# TUDSSL_condenar__Hardware_PCBs_Mainboard.net
KiCad netlist of a schematic drawn in Altium Designer
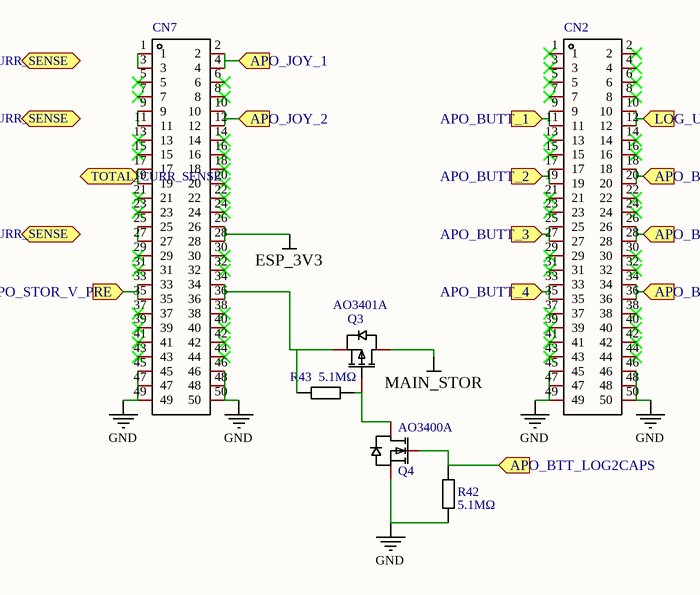
[diagram p0: TUDSSL_condenar__Hardware_PCBs_Mainboard_Board_TUD-V2-EnergyHarvestingConsole_TUD-EnergyHarvestingConsole_1__5_Logging.schdoc]

(export (version "E")
  (design (tool "Eeschema 10.0.6"))
  (components
    (comp (ref "CN2")
      (value "DF40C-50DS-0.4V(51)")
      (fields (field (name "MANUFACTURER") "HRS(广濑)"))
      (libsource (lib "altium-import") (part "root_0_DF40C-50DS-0.4V(51)_"))
    )
    (comp (ref "CN7")
      (value "DF40C-50DS-0.4V(51)")
      (fields (field (name "MANUFACTURER") "HRS(广濑)"))
      (libsource (lib "altium-import") (part "root_0_DF40C-50DS-0.4V(51)_"))
    )
    (comp (ref "Q3")
      (value "AO3401A")
      (fields (field (name "NAME") "AO3401A") (field (name "MANUFACTURER") "AOS"))
      (libsource (lib "altium-import") (part "root_1_AO3401A_"))
    )
    (comp (ref "Q4")
      (value "AO3400A")
      (fields (field (name "NAME") "AO3400A") (field (name "MANUFACTURER") "HUASHUO(华朔)"))
      (libsource (lib "altium-import") (part "root_0_mirrored_AO3400A_"))
    )
    (comp (ref "R42")
      (value "5.1MΩ")
      (fields
        (field (name "NAME") "5.1MΩ")
        (field (name "MANUFACTURER") "UniOhm")
        (field (name "MANUFACTURER PART") "0603WAF5104T5E")
      )
      (libsource (lib "altium-import") (part "root_1_0603WAF5104T5E_"))
    )
    (comp (ref "R43")
      (value "5.1MΩ")
      (fields
        (field (name "NAME") "5.1MΩ")
        (field (name "MANUFACTURER") "UniOhm")
        (field (name "MANUFACTURER PART") "0603WAF5104T5E")
      )
      (libsource (lib "altium-import") (part "root_0_0603WAF5104T5E_"))
    )
  )
  (nets
    (net (code "1") (name "/APO_BTT_LOG2CAPS") (class "Default")
      (node (ref "Q4") (pin "1") (pinfunction "G_1") (pintype "passive"))
      (node (ref "R42") (pin "1") (pinfunction "1_1") (pintype "passive"))
    )
    (net (code "2") (name "/APO_BUTT_1") (class "Default")
      (node (ref "CN2") (pin "11") (pinfunction "11_11") (pintype "passive"))
      (node (ref "CN2") (pin "9") (pinfunction "9_9") (pintype "passive"))
    )
    (net (code "3") (name "/APO_BUTT_2") (class "Default")
      (node (ref "CN2") (pin "17") (pinfunction "17_17") (pintype "passive"))
      (node (ref "CN2") (pin "19") (pinfunction "19_19") (pintype "passive"))
    )
    (net (code "4") (name "/APO_BUTT_3") (class "Default")
      (node (ref "CN2") (pin "25") (pinfunction "25_25") (pintype "passive"))
      (node (ref "CN2") (pin "27") (pinfunction "27_27") (pintype "passive"))
    )
    (net (code "5") (name "/APO_BUTT_4") (class "Default")
      (node (ref "CN2") (pin "33") (pinfunction "33_33") (pintype "passive"))
      (node (ref "CN2") (pin "35") (pinfunction "35_35") (pintype "passive"))
    )
    (net (code "6") (name "/APO_BUTT_5") (class "Default")
      (node (ref "CN2") (pin "34") (pinfunction "34_34") (pintype "passive"))
      (node (ref "CN2") (pin "36") (pinfunction "36_36") (pintype "passive"))
    )
    (net (code "7") (name "/APO_BUTT_6") (class "Default")
      (node (ref "CN2") (pin "26") (pinfunction "26_26") (pintype "passive"))
      (node (ref "CN2") (pin "28") (pinfunction "28_28") (pintype "passive"))
    )
    (net (code "8") (name "/APO_BUTT_7") (class "Default")
      (node (ref "CN2") (pin "18") (pinfunction "18_18") (pintype "passive"))
      (node (ref "CN2") (pin "20") (pinfunction "20_20") (pintype "passive"))
    )
    (net (code "9") (name "/APO_JOY_1") (class "Default")
      (node (ref "CN7") (pin "2") (pinfunction "2_2") (pintype "passive"))
      (node (ref "CN7") (pin "4") (pinfunction "4_4") (pintype "passive"))
    )
    (net (code "10") (name "/APO_JOY_2") (class "Default")
      (node (ref "CN7") (pin "10") (pinfunction "10_10") (pintype "passive"))
      (node (ref "CN7") (pin "12") (pinfunction "12_12") (pintype "passive"))
    )
    (net (code "11") (name "/APO_STOR_V_PRE") (class "Default")
      (node (ref "CN7") (pin "33") (pinfunction "33_33") (pintype "passive"))
      (node (ref "CN7") (pin "35") (pinfunction "35_35") (pintype "passive"))
    )
    (net (code "14") (name "/LOG_UART_RX") (class "Default")
      (node (ref "CN2") (pin "10") (pinfunction "10_10") (pintype "passive"))
      (node (ref "CN2") (pin "12") (pinfunction "12_12") (pintype "passive"))
    )
    (net (code "17") (name "ESP_3V3") (class "Default")
      (node (ref "CN7") (pin "26") (pinfunction "26_26") (pintype "passive"))
      (node (ref "CN7") (pin "28") (pinfunction "28_28") (pintype "passive"))
    )
    (net (code "18") (name "GND") (class "Default")
      (node (ref "CN2") (pin "45") (pinfunction "45_45") (pintype "passive"))
      (node (ref "CN2") (pin "46") (pinfunction "46_46") (pintype "passive"))
      (node (ref "CN2") (pin "47") (pinfunction "47_47") (pintype "passive"))
      (node (ref "CN2") (pin "48") (pinfunction "48_48") (pintype "passive"))
      (node (ref "CN2") (pin "49") (pinfunction "49_49") (pintype "passive"))
      (node (ref "CN2") (pin "50") (pinfunction "50_50") (pintype "passive"))
      (node (ref "CN7") (pin "45") (pinfunction "45_45") (pintype "passive"))
      (node (ref "CN7") (pin "46") (pinfunction "46_46") (pintype "passive"))
      (node (ref "CN7") (pin "47") (pinfunction "47_47") (pintype "passive"))
      (node (ref "CN7") (pin "48") (pinfunction "48_48") (pintype "passive"))
      (node (ref "CN7") (pin "49") (pinfunction "49_49") (pintype "passive"))
      (node (ref "CN7") (pin "50") (pinfunction "50_50") (pintype "passive"))
      (node (ref "Q4") (pin "2") (pinfunction "S_2") (pintype "passive"))
      (node (ref "R42") (pin "2") (pinfunction "2_2") (pintype "passive"))
    )
    (net (code "19") (name "MAIN_STOR") (class "Default")
      (node (ref "Q3") (pin "3") (pinfunction "D_3") (pintype "passive"))
    )
    (net (code "20") (name "Net-(CN7-Pad1)") (class "Default")
      (node (ref "CN7") (pin "1") (pinfunction "1_1") (pintype "passive"))
      (node (ref "CN7") (pin "3") (pinfunction "3_3") (pintype "passive"))
    )
    (net (code "21") (name "Net-(CN7-Pad11)") (class "Default")
      (node (ref "CN7") (pin "11") (pinfunction "11_11") (pintype "passive"))
      (node (ref "CN7") (pin "9") (pinfunction "9_9") (pintype "passive"))
    )
    (net (code "22") (name "Net-(CN7-Pad17)") (class "Default")
      (node (ref "CN7") (pin "17") (pinfunction "17_17") (pintype "passive"))
      (node (ref "CN7") (pin "19") (pinfunction "19_19") (pintype "passive"))
    )
    (net (code "23") (name "Net-(CN7-Pad25)") (class "Default")
      (node (ref "CN7") (pin "25") (pinfunction "25_25") (pintype "passive"))
      (node (ref "CN7") (pin "27") (pinfunction "27_27") (pintype "passive"))
    )
    (net (code "24") (name "Net-(Q3-G)") (class "Default")
      (node (ref "Q3") (pin "1") (pinfunction "G_1") (pintype "passive"))
      (node (ref "Q4") (pin "3") (pinfunction "D_3") (pintype "passive"))
      (node (ref "R43") (pin "1") (pinfunction "1_1") (pintype "passive"))
    )
    (net (code "25") (name "Net-(Q3-S)") (class "Default")
      (node (ref "CN7") (pin "34") (pinfunction "34_34") (pintype "passive"))
      (node (ref "CN7") (pin "36") (pinfunction "36_36") (pintype "passive"))
      (node (ref "Q3") (pin "2") (pinfunction "S_2") (pintype "passive"))
      (node (ref "R43") (pin "2") (pinfunction "2_2") (pintype "passive"))
    )
    (net (code "26") (name "unconnected-(CN2-Pad1)") (class "Default")
      (node (ref "CN2") (pin "1") (pinfunction "1_1") (pintype "passive+no_connect"))
    )
    (net (code "27") (name "unconnected-(CN2-Pad2)") (class "Default")
      (node (ref "CN2") (pin "2") (pinfunction "2_2") (pintype "passive+no_connect"))
    )
    (net (code "28") (name "unconnected-(CN2-Pad3)") (class "Default")
      (node (ref "CN2") (pin "3") (pinfunction "3_3") (pintype "passive+no_connect"))
    )
    (net (code "29") (name "unconnected-(CN2-Pad4)") (class "Default")
      (node (ref "CN2") (pin "4") (pinfunction "4_4") (pintype "passive+no_connect"))
    )
    (net (code "30") (name "unconnected-(CN2-Pad5)") (class "Default")
      (node (ref "CN2") (pin "5") (pinfunction "5_5") (pintype "passive+no_connect"))
    )
    (net (code "31") (name "unconnected-(CN2-Pad6)") (class "Default")
      (node (ref "CN2") (pin "6") (pinfunction "6_6") (pintype "passive+no_connect"))
    )
    (net (code "32") (name "unconnected-(CN2-Pad7)") (class "Default")
      (node (ref "CN2") (pin "7") (pinfunction "7_7") (pintype "passive+no_connect"))
    )
    (net (code "33") (name "unconnected-(CN2-Pad8)") (class "Default")
      (node (ref "CN2") (pin "8") (pinfunction "8_8") (pintype "passive+no_connect"))
    )
    (net (code "34") (name "unconnected-(CN2-Pad13)") (class "Default")
      (node (ref "CN2") (pin "13") (pinfunction "13_13") (pintype "passive+no_connect"))
    )
    (net (code "35") (name "unconnected-(CN2-Pad14)") (class "Default")
      (node (ref "CN2") (pin "14") (pinfunction "14_14") (pintype "passive+no_connect"))
    )
    (net (code "36") (name "unconnected-(CN2-Pad15)") (class "Default")
      (node (ref "CN2") (pin "15") (pinfunction "15_15") (pintype "passive+no_connect"))
    )
    (net (code "37") (name "unconnected-(CN2-Pad16)") (class "Default")
      (node (ref "CN2") (pin "16") (pinfunction "16_16") (pintype "passive+no_connect"))
    )
    (net (code "38") (name "unconnected-(CN2-Pad21)") (class "Default")
      (node (ref "CN2") (pin "21") (pinfunction "21_21") (pintype "passive+no_connect"))
    )
    (net (code "39") (name "unconnected-(CN2-Pad22)") (class "Default")
      (node (ref "CN2") (pin "22") (pinfunction "22_22") (pintype "passive+no_connect"))
    )
    (net (code "40") (name "unconnected-(CN2-Pad23)") (class "Default")
      (node (ref "CN2") (pin "23") (pinfunction "23_23") (pintype "passive+no_connect"))
    )
    (net (code "41") (name "unconnected-(CN2-Pad24)") (class "Default")
      (node (ref "CN2") (pin "24") (pinfunction "24_24") (pintype "passive+no_connect"))
    )
    (net (code "42") (name "unconnected-(CN2-Pad29)") (class "Default")
      (node (ref "CN2") (pin "29") (pinfunction "29_29") (pintype "passive+no_connect"))
    )
    (net (code "43") (name "unconnected-(CN2-Pad30)") (class "Default")
      (node (ref "CN2") (pin "30") (pinfunction "30_30") (pintype "passive+no_connect"))
    )
    (net (code "44") (name "unconnected-(CN2-Pad31)") (class "Default")
      (node (ref "CN2") (pin "31") (pinfunction "31_31") (pintype "passive+no_connect"))
    )
    (net (code "45") (name "unconnected-(CN2-Pad32)") (class "Default")
      (node (ref "CN2") (pin "32") (pinfunction "32_32") (pintype "passive+no_connect"))
    )
    (net (code "46") (name "unconnected-(CN2-Pad37)") (class "Default")
      (node (ref "CN2") (pin "37") (pinfunction "37_37") (pintype "passive+no_connect"))
    )
    (net (code "47") (name "unconnected-(CN2-Pad38)") (class "Default")
      (node (ref "CN2") (pin "38") (pinfunction "38_38") (pintype "passive+no_connect"))
    )
    (net (code "48") (name "unconnected-(CN2-Pad39)") (class "Default")
      (node (ref "CN2") (pin "39") (pinfunction "39_39") (pintype "passive+no_connect"))
    )
    (net (code "49") (name "unconnected-(CN2-Pad40)") (class "Default")
      (node (ref "CN2") (pin "40") (pinfunction "40_40") (pintype "passive+no_connect"))
    )
    (net (code "50") (name "unconnected-(CN2-Pad41)") (class "Default")
      (node (ref "CN2") (pin "41") (pinfunction "41_41") (pintype "passive+no_connect"))
    )
    (net (code "51") (name "unconnected-(CN2-Pad42)") (class "Default")
      (node (ref "CN2") (pin "42") (pinfunction "42_42") (pintype "passive+no_connect"))
    )
    (net (code "52") (name "unconnected-(CN2-Pad43)") (class "Default")
      (node (ref "CN2") (pin "43") (pinfunction "43_43") (pintype "passive+no_connect"))
    )
    (net (code "53") (name "unconnected-(CN2-Pad44)") (class "Default")
      (node (ref "CN2") (pin "44") (pinfunction "44_44") (pintype "passive+no_connect"))
    )
    (net (code "54") (name "unconnected-(CN7-Pad5)") (class "Default")
      (node (ref "CN7") (pin "5") (pinfunction "5_5") (pintype "passive+no_connect"))
    )
    (net (code "55") (name "unconnected-(CN7-Pad6)") (class "Default")
      (node (ref "CN7") (pin "6") (pinfunction "6_6") (pintype "passive+no_connect"))
    )
    (net (code "56") (name "unconnected-(CN7-Pad7)") (class "Default")
      (node (ref "CN7") (pin "7") (pinfunction "7_7") (pintype "passive+no_connect"))
    )
    (net (code "57") (name "unconnected-(CN7-Pad8)") (class "Default")
      (node (ref "CN7") (pin "8") (pinfunction "8_8") (pintype "passive+no_connect"))
    )
    (net (code "58") (name "unconnected-(CN7-Pad13)") (class "Default")
      (node (ref "CN7") (pin "13") (pinfunction "13_13") (pintype "passive+no_connect"))
    )
    (net (code "59") (name "unconnected-(CN7-Pad14)") (class "Default")
      (node (ref "CN7") (pin "14") (pinfunction "14_14") (pintype "passive+no_connect"))
    )
    (net (code "60") (name "unconnected-(CN7-Pad15)") (class "Default")
      (node (ref "CN7") (pin "15") (pinfunction "15_15") (pintype "passive+no_connect"))
    )
    (net (code "61") (name "unconnected-(CN7-Pad16)") (class "Default")
      (node (ref "CN7") (pin "16") (pinfunction "16_16") (pintype "passive+no_connect"))
    )
    (net (code "62") (name "unconnected-(CN7-Pad18)") (class "Default")
      (node (ref "CN7") (pin "18") (pinfunction "18_18") (pintype "passive+no_connect"))
    )
    (net (code "63") (name "unconnected-(CN7-Pad20)") (class "Default")
      (node (ref "CN7") (pin "20") (pinfunction "20_20") (pintype "passive+no_connect"))
    )
    (net (code "64") (name "unconnected-(CN7-Pad21)") (class "Default")
      (node (ref "CN7") (pin "21") (pinfunction "21_21") (pintype "passive+no_connect"))
    )
    (net (code "65") (name "unconnected-(CN7-Pad22)") (class "Default")
      (node (ref "CN7") (pin "22") (pinfunction "22_22") (pintype "passive+no_connect"))
    )
    (net (code "66") (name "unconnected-(CN7-Pad23)") (class "Default")
      (node (ref "CN7") (pin "23") (pinfunction "23_23") (pintype "passive+no_connect"))
    )
    (net (code "67") (name "unconnected-(CN7-Pad24)") (class "Default")
      (node (ref "CN7") (pin "24") (pinfunction "24_24") (pintype "passive+no_connect"))
    )
    (net (code "68") (name "unconnected-(CN7-Pad29)") (class "Default")
      (node (ref "CN7") (pin "29") (pinfunction "29_29") (pintype "passive+no_connect"))
    )
    (net (code "69") (name "unconnected-(CN7-Pad30)") (class "Default")
      (node (ref "CN7") (pin "30") (pinfunction "30_30") (pintype "passive+no_connect"))
    )
    (net (code "70") (name "unconnected-(CN7-Pad31)") (class "Default")
      (node (ref "CN7") (pin "31") (pinfunction "31_31") (pintype "passive+no_connect"))
    )
    (net (code "71") (name "unconnected-(CN7-Pad32)") (class "Default")
      (node (ref "CN7") (pin "32") (pinfunction "32_32") (pintype "passive+no_connect"))
    )
    (net (code "72") (name "unconnected-(CN7-Pad37)") (class "Default")
      (node (ref "CN7") (pin "37") (pinfunction "37_37") (pintype "passive+no_connect"))
    )
    (net (code "73") (name "unconnected-(CN7-Pad38)") (class "Default")
      (node (ref "CN7") (pin "38") (pinfunction "38_38") (pintype "passive+no_connect"))
    )
    (net (code "74") (name "unconnected-(CN7-Pad39)") (class "Default")
      (node (ref "CN7") (pin "39") (pinfunction "39_39") (pintype "passive+no_connect"))
    )
    (net (code "75") (name "unconnected-(CN7-Pad40)") (class "Default")
      (node (ref "CN7") (pin "40") (pinfunction "40_40") (pintype "passive+no_connect"))
    )
    (net (code "76") (name "unconnected-(CN7-Pad41)") (class "Default")
      (node (ref "CN7") (pin "41") (pinfunction "41_41") (pintype "passive+no_connect"))
    )
    (net (code "77") (name "unconnected-(CN7-Pad42)") (class "Default")
      (node (ref "CN7") (pin "42") (pinfunction "42_42") (pintype "passive+no_connect"))
    )
    (net (code "78") (name "unconnected-(CN7-Pad43)") (class "Default")
      (node (ref "CN7") (pin "43") (pinfunction "43_43") (pintype "passive+no_connect"))
    )
    (net (code "79") (name "unconnected-(CN7-Pad44)") (class "Default")
      (node (ref "CN7") (pin "44") (pinfunction "44_44") (pintype "passive+no_connect"))
    )
  )
)
